# ESP32_v1_1_Schematic.net
KiCad netlist of a schematic drawn in EAGLE
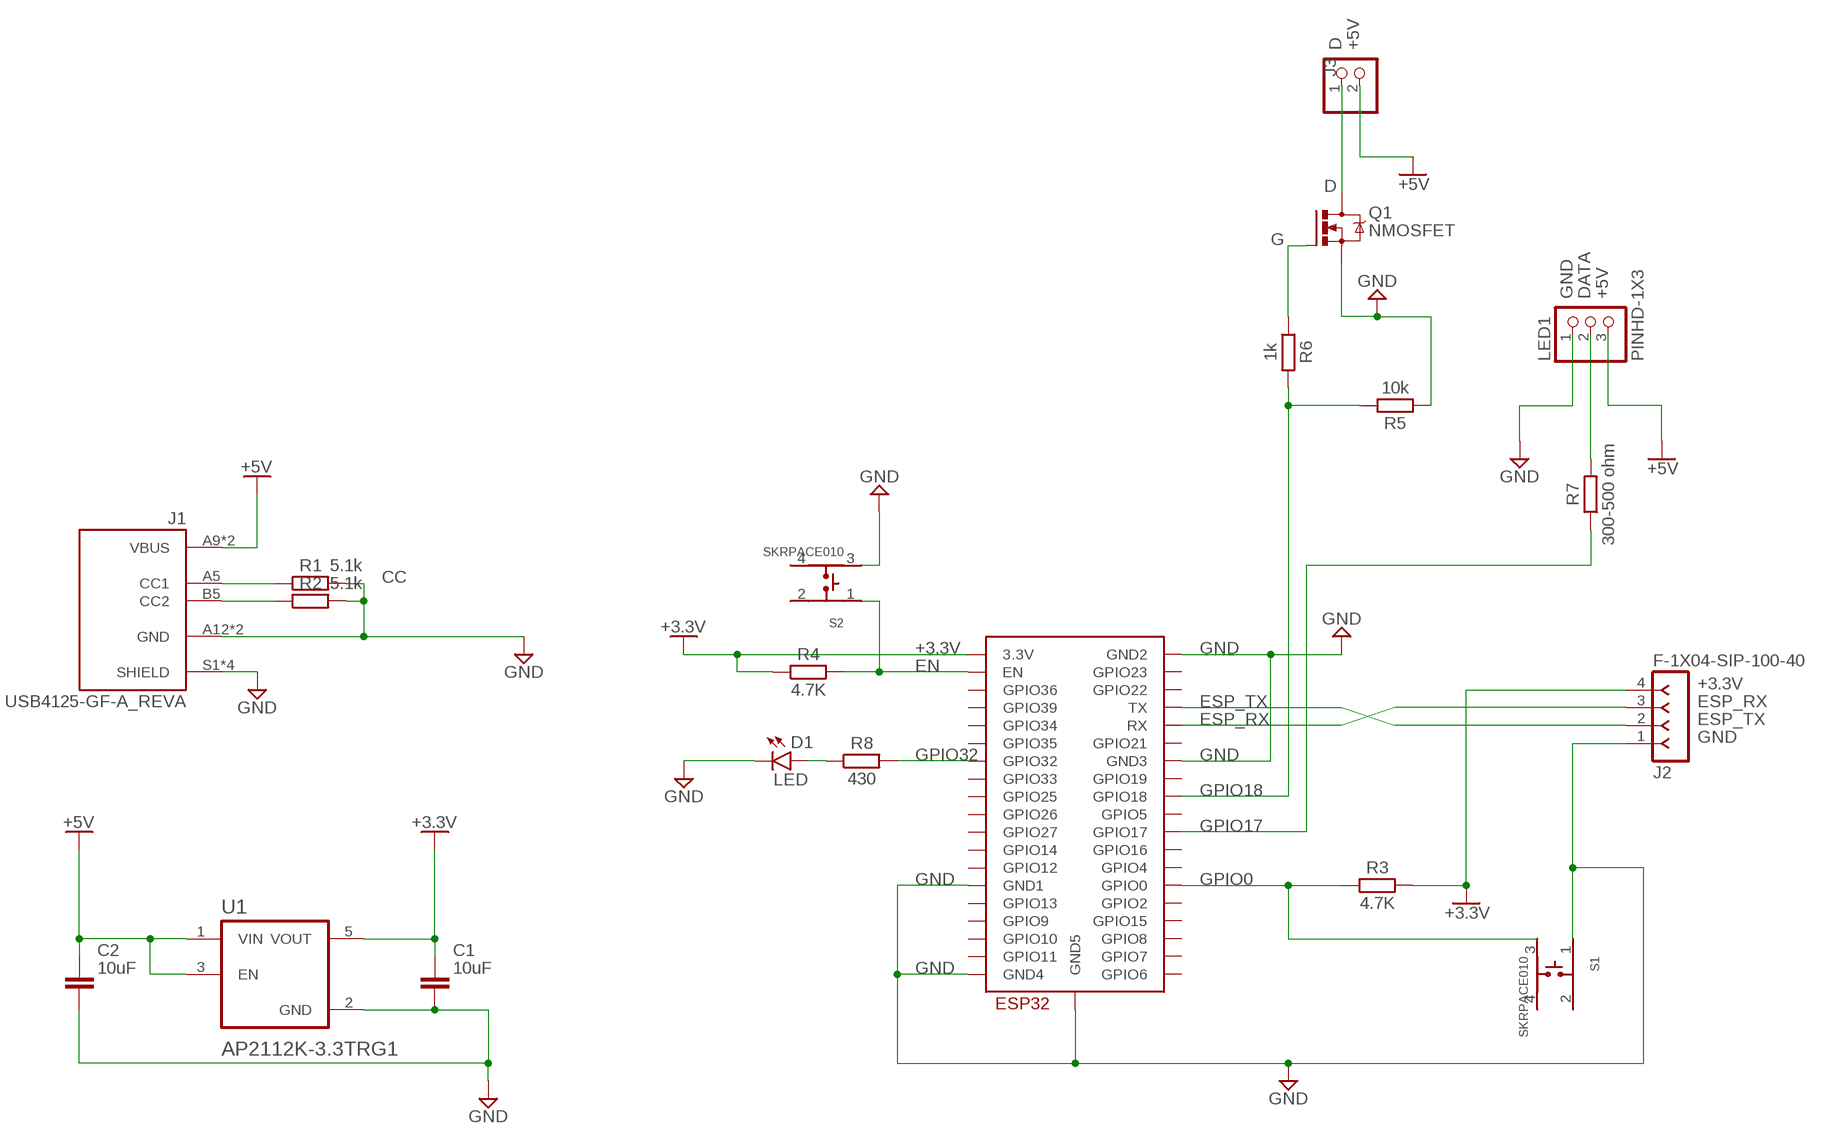
[diagram p0: schematic, sheet 1]

(export (version "E")
  (design (tool "Eeschema 10.0.6"))
  (components
    (comp (ref "C1")
      (value "10uF")
      (footprint "eagle-import:CAPC1608X85")
      (libsource (lib "eagle-import") (part "CCHIP-0603(1608-METRIC)_"))
    )
    (comp (ref "C2")
      (value "10uF")
      (footprint "eagle-import:CAPC1608X85")
      (libsource (lib "eagle-import") (part "CCHIP-0603(1608-METRIC)_"))
    )
    (comp (ref "D1")
      (value "LED")
      (footprint "eagle-import:LEDC1608X80N_FLAT-R")
      (libsource (lib "eagle-import") (part "CHIP-FLAT-R_0603-0.80MM"))
    )
    (comp (ref "J1")
      (value "USB4125-GF-A_REVA")
      (footprint "eagle-import:GCT_USB4125-GF-A_REVA")
      (fields (field (name "MF") "Global Connector Technology") (field (name "MP") "USB4125-GF-A"))
      (libsource (lib "eagle-import") (part "USB4125-GF-A_REVA"))
    )
    (comp (ref "J2")
      (value "F-1X04-SIP-100-40")
      (footprint "eagle-import:SIP-100-04-40")
      (libsource (lib "eagle-import") (part "F-1X04-SIP-100-40"))
    )
    (comp (ref "J3")
      (value "PINHD-1X2")
      (footprint "eagle-import:1X02")
      (libsource (lib "eagle-import") (part "PINHD-1X2"))
    )
    (comp (ref "LED1")
      (value "PINHD-1X3")
      (footprint "eagle-import:1X03")
      (libsource (lib "eagle-import") (part "PINHD-1X3"))
    )
    (comp (ref "Q1")
      (value "NMOSFET")
      (footprint "eagle-import:SOT23")
      (libsource (lib "eagle-import") (part "NMOSFETSOT23_"))
    )
    (comp (ref "R1")
      (value "5.1k")
      (footprint "eagle-import:RESC1608X60")
      (libsource (lib "eagle-import") (part "RCHIP-0603(1608-METRIC)_"))
    )
    (comp (ref "R2")
      (value "5.1k")
      (footprint "eagle-import:RESC1608X60")
      (libsource (lib "eagle-import") (part "RCHIP-0603(1608-METRIC)_"))
    )
    (comp (ref "R3")
      (value "4.7K")
      (footprint "eagle-import:RESC1608X60")
      (libsource (lib "eagle-import") (part "RCHIP-0603(1608-METRIC)_"))
    )
    (comp (ref "R4")
      (value "4.7K")
      (footprint "eagle-import:RESC1608X60")
      (libsource (lib "eagle-import") (part "RCHIP-0603(1608-METRIC)_"))
    )
    (comp (ref "R5")
      (value "10k")
      (footprint "eagle-import:RESC1608X60")
      (libsource (lib "eagle-import") (part "RCHIP-0603(1608-METRIC)_"))
    )
    (comp (ref "R6")
      (value "1k")
      (footprint "eagle-import:RESC1608X60")
      (libsource (lib "eagle-import") (part "RCHIP-0603(1608-METRIC)_"))
    )
    (comp (ref "R7")
      (value "300-500 ohm")
      (footprint "eagle-import:RESC1608X60")
      (libsource (lib "eagle-import") (part "RCHIP-0603(1608-METRIC)_"))
    )
    (comp (ref "R8")
      (value "430")
      (footprint "eagle-import:RESC1608X60")
      (libsource (lib "eagle-import") (part "RCHIP-0603(1608-METRIC)_"))
    )
    (comp (ref "S1")
      (value "SKRPACE010")
      (footprint "eagle-import:SW_SKRPACE010")
      (fields (field (name "MANUFACTURER") "ALPS"))
      (libsource (lib "eagle-import") (part "SKRPACE010"))
    )
    (comp (ref "S2")
      (value "SKRPACE010")
      (footprint "eagle-import:SW_SKRPACE010")
      (fields (field (name "MANUFACTURER") "ALPS"))
      (libsource (lib "eagle-import") (part "SKRPACE010"))
    )
    (comp (ref "U1")
      (value "AP2112K-3.3TRG1")
      (footprint "eagle-import:SOT95P285X140-5N")
      (fields (field (name "MANUFACTURER") "Diodes Inc."))
      (libsource (lib "eagle-import") (part "AP2112K-3.3TRG1"))
    )
    (comp (ref "U2")
      (value "ESP32-WROOM")
      (footprint "eagle-import:ESP32-WROOM")
      (libsource (lib "eagle-import") (part "ESP32-WROOM"))
    )
  )
  (nets
    (net (code "1") (name "+3.3V") (class "Default")
      (node (ref "C1") (pin "1") (pinfunction "1_1") (pintype "passive"))
      (node (ref "J2") (pin "4") (pinfunction "4_4") (pintype "passive"))
      (node (ref "R3") (pin "2") (pinfunction "2_2") (pintype "passive"))
      (node (ref "R4") (pin "1") (pinfunction "1_1") (pintype "passive"))
      (node (ref "U1") (pin "5") (pinfunction "VOUT_5") (pintype "power_in"))
      (node (ref "U2") (pin "3V3") (pinfunction "3.3V_3V3") (pintype "bidirectional"))
    )
    (net (code "2") (name "+5V") (class "Default")
      (node (ref "C2") (pin "1") (pinfunction "1_1") (pintype "passive"))
      (node (ref "J1") (pin "A9") (pinfunction "VBUS_A9") (pintype "power_in"))
      (node (ref "J1") (pin "B9") (pinfunction "VBUS_B9") (pintype "power_in"))
      (node (ref "J3") (pin "2") (pinfunction "2_2") (pintype "passive"))
      (node (ref "LED1") (pin "3") (pinfunction "3_3") (pintype "passive"))
      (node (ref "U1") (pin "1") (pinfunction "VIN_1") (pintype "power_in"))
      (node (ref "U1") (pin "3") (pinfunction "EN_3") (pintype "input"))
    )
    (net (code "3") (name "/CC") (class "Default")
      (node (ref "J1") (pin "A5") (pinfunction "CC1_A5") (pintype "bidirectional"))
      (node (ref "R1") (pin "1") (pinfunction "1_1") (pintype "passive"))
    )
    (net (code "4") (name "/D") (class "Default")
      (node (ref "J3") (pin "1") (pinfunction "1_1") (pintype "passive"))
      (node (ref "Q1") (pin "3") (pinfunction "D_3") (pintype "passive"))
    )
    (net (code "5") (name "/DATA") (class "Default")
      (node (ref "LED1") (pin "2") (pinfunction "2_2") (pintype "passive"))
      (node (ref "R7") (pin "2") (pinfunction "2_2") (pintype "passive"))
    )
    (net (code "6") (name "/EN") (class "Default")
      (node (ref "R4") (pin "2") (pinfunction "2_2") (pintype "passive"))
      (node (ref "S2") (pin "1") (pinfunction "1_1") (pintype "bidirectional"))
      (node (ref "U2") (pin "EN") (pinfunction "EN_EN") (pintype "bidirectional"))
    )
    (net (code "7") (name "/ESP_RX") (class "Default")
      (node (ref "J2") (pin "3") (pinfunction "3_3") (pintype "passive"))
      (node (ref "U2") (pin "RX") (pinfunction "RX_RX") (pintype "bidirectional"))
    )
    (net (code "8") (name "/ESP_TX") (class "Default")
      (node (ref "J2") (pin "2") (pinfunction "2_2") (pintype "passive"))
      (node (ref "U2") (pin "TX") (pinfunction "TX_TX") (pintype "bidirectional"))
    )
    (net (code "9") (name "/G") (class "Default")
      (node (ref "Q1") (pin "1") (pinfunction "G_1") (pintype "passive"))
      (node (ref "R6") (pin "1") (pinfunction "1_1") (pintype "passive"))
    )
    (net (code "10") (name "/GPIO0") (class "Default")
      (node (ref "R3") (pin "1") (pinfunction "1_1") (pintype "passive"))
      (node (ref "S1") (pin "3") (pinfunction "3_3") (pintype "bidirectional"))
      (node (ref "U2") (pin "IO0") (pinfunction "GPIO0_IO0") (pintype "bidirectional"))
    )
    (net (code "11") (name "/GPIO17") (class "Default")
      (node (ref "R7") (pin "1") (pinfunction "1_1") (pintype "passive"))
      (node (ref "U2") (pin "IO17") (pinfunction "GPIO17_IO17") (pintype "bidirectional"))
    )
    (net (code "12") (name "/GPIO18") (class "Default")
      (node (ref "R5") (pin "2") (pinfunction "2_2") (pintype "passive"))
      (node (ref "R6") (pin "2") (pinfunction "2_2") (pintype "passive"))
      (node (ref "U2") (pin "IO18") (pinfunction "GPIO18_IO18") (pintype "bidirectional"))
    )
    (net (code "13") (name "/GPIO32") (class "Default")
      (node (ref "R8") (pin "2") (pinfunction "2_2") (pintype "passive"))
      (node (ref "U2") (pin "IO32") (pinfunction "GPIO32_IO32") (pintype "bidirectional"))
    )
    (net (code "14") (name "GND") (class "Default")
      (node (ref "C1") (pin "2") (pinfunction "2_2") (pintype "passive"))
      (node (ref "C2") (pin "2") (pinfunction "2_2") (pintype "passive"))
      (node (ref "D1") (pin "C") (pinfunction "C_C") (pintype "passive"))
      (node (ref "J1") (pin "A12") (pinfunction "GND_A12") (pintype "power_in"))
      (node (ref "J1") (pin "B12") (pinfunction "GND_B12") (pintype "power_in"))
      (node (ref "J1") (pin "S1") (pinfunction "SHIELD_S1") (pintype "passive"))
      (node (ref "J1") (pin "S2") (pinfunction "SHIELD_S2") (pintype "passive"))
      (node (ref "J1") (pin "S3") (pinfunction "SHIELD_S3") (pintype "passive"))
      (node (ref "J1") (pin "S4") (pinfunction "SHIELD_S4") (pintype "passive"))
      (node (ref "J2") (pin "1") (pinfunction "1_1") (pintype "passive"))
      (node (ref "LED1") (pin "1") (pinfunction "1_1") (pintype "passive"))
      (node (ref "Q1") (pin "2") (pinfunction "S_2") (pintype "passive"))
      (node (ref "R1") (pin "2") (pinfunction "2_2") (pintype "passive"))
      (node (ref "R2") (pin "2") (pinfunction "2_2") (pintype "passive"))
      (node (ref "R5") (pin "1") (pinfunction "1_1") (pintype "passive"))
      (node (ref "S1") (pin "1") (pinfunction "1_1") (pintype "bidirectional"))
      (node (ref "S2") (pin "3") (pinfunction "3_3") (pintype "bidirectional"))
      (node (ref "U1") (pin "2") (pinfunction "GND_2") (pintype "power_in"))
      (node (ref "U2") (pin "GND1") (pinfunction "GND1_GND1") (pintype "bidirectional"))
      (node (ref "U2") (pin "GND2") (pinfunction "GND2_GND2") (pintype "bidirectional"))
      (node (ref "U2") (pin "GND3") (pinfunction "GND3_GND3") (pintype "bidirectional"))
      (node (ref "U2") (pin "GND4") (pinfunction "GND4_GND4") (pintype "bidirectional"))
      (node (ref "U2") (pin "GND5") (pinfunction "GND5_GND5") (pintype "bidirectional"))
    )
    (net (code "15") (name "Net-(D1-PadA)") (class "Default")
      (node (ref "D1") (pin "A") (pinfunction "A_A") (pintype "passive"))
      (node (ref "R8") (pin "1") (pinfunction "1_1") (pintype "passive"))
    )
    (net (code "16") (name "Net-(J1-CC2)") (class "Default")
      (node (ref "J1") (pin "B5") (pinfunction "CC2_B5") (pintype "bidirectional"))
      (node (ref "R2") (pin "1") (pinfunction "1_1") (pintype "passive"))
    )
    (net (code "17") (name "unconnected-(S1-Pad2)") (class "Default")
      (node (ref "S1") (pin "2") (pinfunction "2_2") (pintype "bidirectional"))
    )
    (net (code "18") (name "unconnected-(S1-Pad4)") (class "Default")
      (node (ref "S1") (pin "4") (pinfunction "4_4") (pintype "bidirectional"))
    )
    (net (code "19") (name "unconnected-(S2-Pad2)") (class "Default")
      (node (ref "S2") (pin "2") (pinfunction "2_2") (pintype "bidirectional"))
    )
    (net (code "20") (name "unconnected-(S2-Pad4)") (class "Default")
      (node (ref "S2") (pin "4") (pinfunction "4_4") (pintype "bidirectional"))
    )
    (net (code "21") (name "unconnected-(U2-GPIO2-PadIO2)") (class "Default")
      (node (ref "U2") (pin "IO2") (pinfunction "GPIO2_IO2") (pintype "bidirectional"))
    )
    (net (code "22") (name "unconnected-(U2-GPIO4-PadIO4)") (class "Default")
      (node (ref "U2") (pin "IO4") (pinfunction "GPIO4_IO4") (pintype "bidirectional"))
    )
    (net (code "23") (name "unconnected-(U2-GPIO5-PadIO5)") (class "Default")
      (node (ref "U2") (pin "IO5") (pinfunction "GPIO5_IO5") (pintype "bidirectional"))
    )
    (net (code "24") (name "unconnected-(U2-GPIO6-PadCLK)") (class "Default")
      (node (ref "U2") (pin "CLK") (pinfunction "GPIO6_CLK") (pintype "bidirectional"))
    )
    (net (code "25") (name "unconnected-(U2-GPIO7-PadSD0)") (class "Default")
      (node (ref "U2") (pin "SD0") (pinfunction "GPIO7_SD0") (pintype "bidirectional"))
    )
    (net (code "26") (name "unconnected-(U2-GPIO8-PadSD1)") (class "Default")
      (node (ref "U2") (pin "SD1") (pinfunction "GPIO8_SD1") (pintype "bidirectional"))
    )
    (net (code "27") (name "unconnected-(U2-GPIO9-PadSD2)") (class "Default")
      (node (ref "U2") (pin "SD2") (pinfunction "GPIO9_SD2") (pintype "bidirectional"))
    )
    (net (code "28") (name "unconnected-(U2-GPIO10-PadSD3)") (class "Default")
      (node (ref "U2") (pin "SD3") (pinfunction "GPIO10_SD3") (pintype "bidirectional"))
    )
    (net (code "29") (name "unconnected-(U2-GPIO11-PadCMD)") (class "Default")
      (node (ref "U2") (pin "CMD") (pinfunction "GPIO11_CMD") (pintype "bidirectional"))
    )
    (net (code "30") (name "unconnected-(U2-GPIO12-PadIO12)") (class "Default")
      (node (ref "U2") (pin "IO12") (pinfunction "GPIO12_IO12") (pintype "bidirectional"))
    )
    (net (code "31") (name "unconnected-(U2-GPIO13-PadIO13)") (class "Default")
      (node (ref "U2") (pin "IO13") (pinfunction "GPIO13_IO13") (pintype "bidirectional"))
    )
    (net (code "32") (name "unconnected-(U2-GPIO14-PadIO14)") (class "Default")
      (node (ref "U2") (pin "IO14") (pinfunction "GPIO14_IO14") (pintype "bidirectional"))
    )
    (net (code "33") (name "unconnected-(U2-GPIO15-PadIO15)") (class "Default")
      (node (ref "U2") (pin "IO15") (pinfunction "GPIO15_IO15") (pintype "bidirectional"))
    )
    (net (code "34") (name "unconnected-(U2-GPIO16-PadIO16)") (class "Default")
      (node (ref "U2") (pin "IO16") (pinfunction "GPIO16_IO16") (pintype "bidirectional"))
    )
    (net (code "35") (name "unconnected-(U2-GPIO19-PadIO19)") (class "Default")
      (node (ref "U2") (pin "IO19") (pinfunction "GPIO19_IO19") (pintype "bidirectional"))
    )
    (net (code "36") (name "unconnected-(U2-GPIO21-PadIO21)") (class "Default")
      (node (ref "U2") (pin "IO21") (pinfunction "GPIO21_IO21") (pintype "bidirectional"))
    )
    (net (code "37") (name "unconnected-(U2-GPIO22-PadIO22)") (class "Default")
      (node (ref "U2") (pin "IO22") (pinfunction "GPIO22_IO22") (pintype "bidirectional"))
    )
    (net (code "38") (name "unconnected-(U2-GPIO23-PadIO23)") (class "Default")
      (node (ref "U2") (pin "IO23") (pinfunction "GPIO23_IO23") (pintype "bidirectional"))
    )
    (net (code "39") (name "unconnected-(U2-GPIO25-PadIO25)") (class "Default")
      (node (ref "U2") (pin "IO25") (pinfunction "GPIO25_IO25") (pintype "bidirectional"))
    )
    (net (code "40") (name "unconnected-(U2-GPIO26-PadIO26)") (class "Default")
      (node (ref "U2") (pin "IO26") (pinfunction "GPIO26_IO26") (pintype "bidirectional"))
    )
    (net (code "41") (name "unconnected-(U2-GPIO27-PadIO27)") (class "Default")
      (node (ref "U2") (pin "IO27") (pinfunction "GPIO27_IO27") (pintype "bidirectional"))
    )
    (net (code "42") (name "unconnected-(U2-GPIO33-PadIO33)") (class "Default")
      (node (ref "U2") (pin "IO33") (pinfunction "GPIO33_IO33") (pintype "bidirectional"))
    )
    (net (code "43") (name "unconnected-(U2-GPIO34-PadIO34)") (class "Default")
      (node (ref "U2") (pin "IO34") (pinfunction "GPIO34_IO34") (pintype "bidirectional"))
    )
    (net (code "44") (name "unconnected-(U2-GPIO35-PadIO35)") (class "Default")
      (node (ref "U2") (pin "IO35") (pinfunction "GPIO35_IO35") (pintype "bidirectional"))
    )
    (net (code "45") (name "unconnected-(U2-GPIO36-PadSENSOR_VP)") (class "Default")
      (node (ref "U2") (pin "SENSOR_VP") (pinfunction "GPIO36_SENSOR_VP") (pintype "bidirectional"))
    )
    (net (code "46") (name "unconnected-(U2-GPIO39-PadSENSOR_VN)") (class "Default")
      (node (ref "U2") (pin "SENSOR_VN") (pinfunction "GPIO39_SENSOR_VN") (pintype "bidirectional"))
    )
  )
)
